# FRDM-Robot-Rev2_1.net
KiCad netlist of a schematic drawn in EAGLE
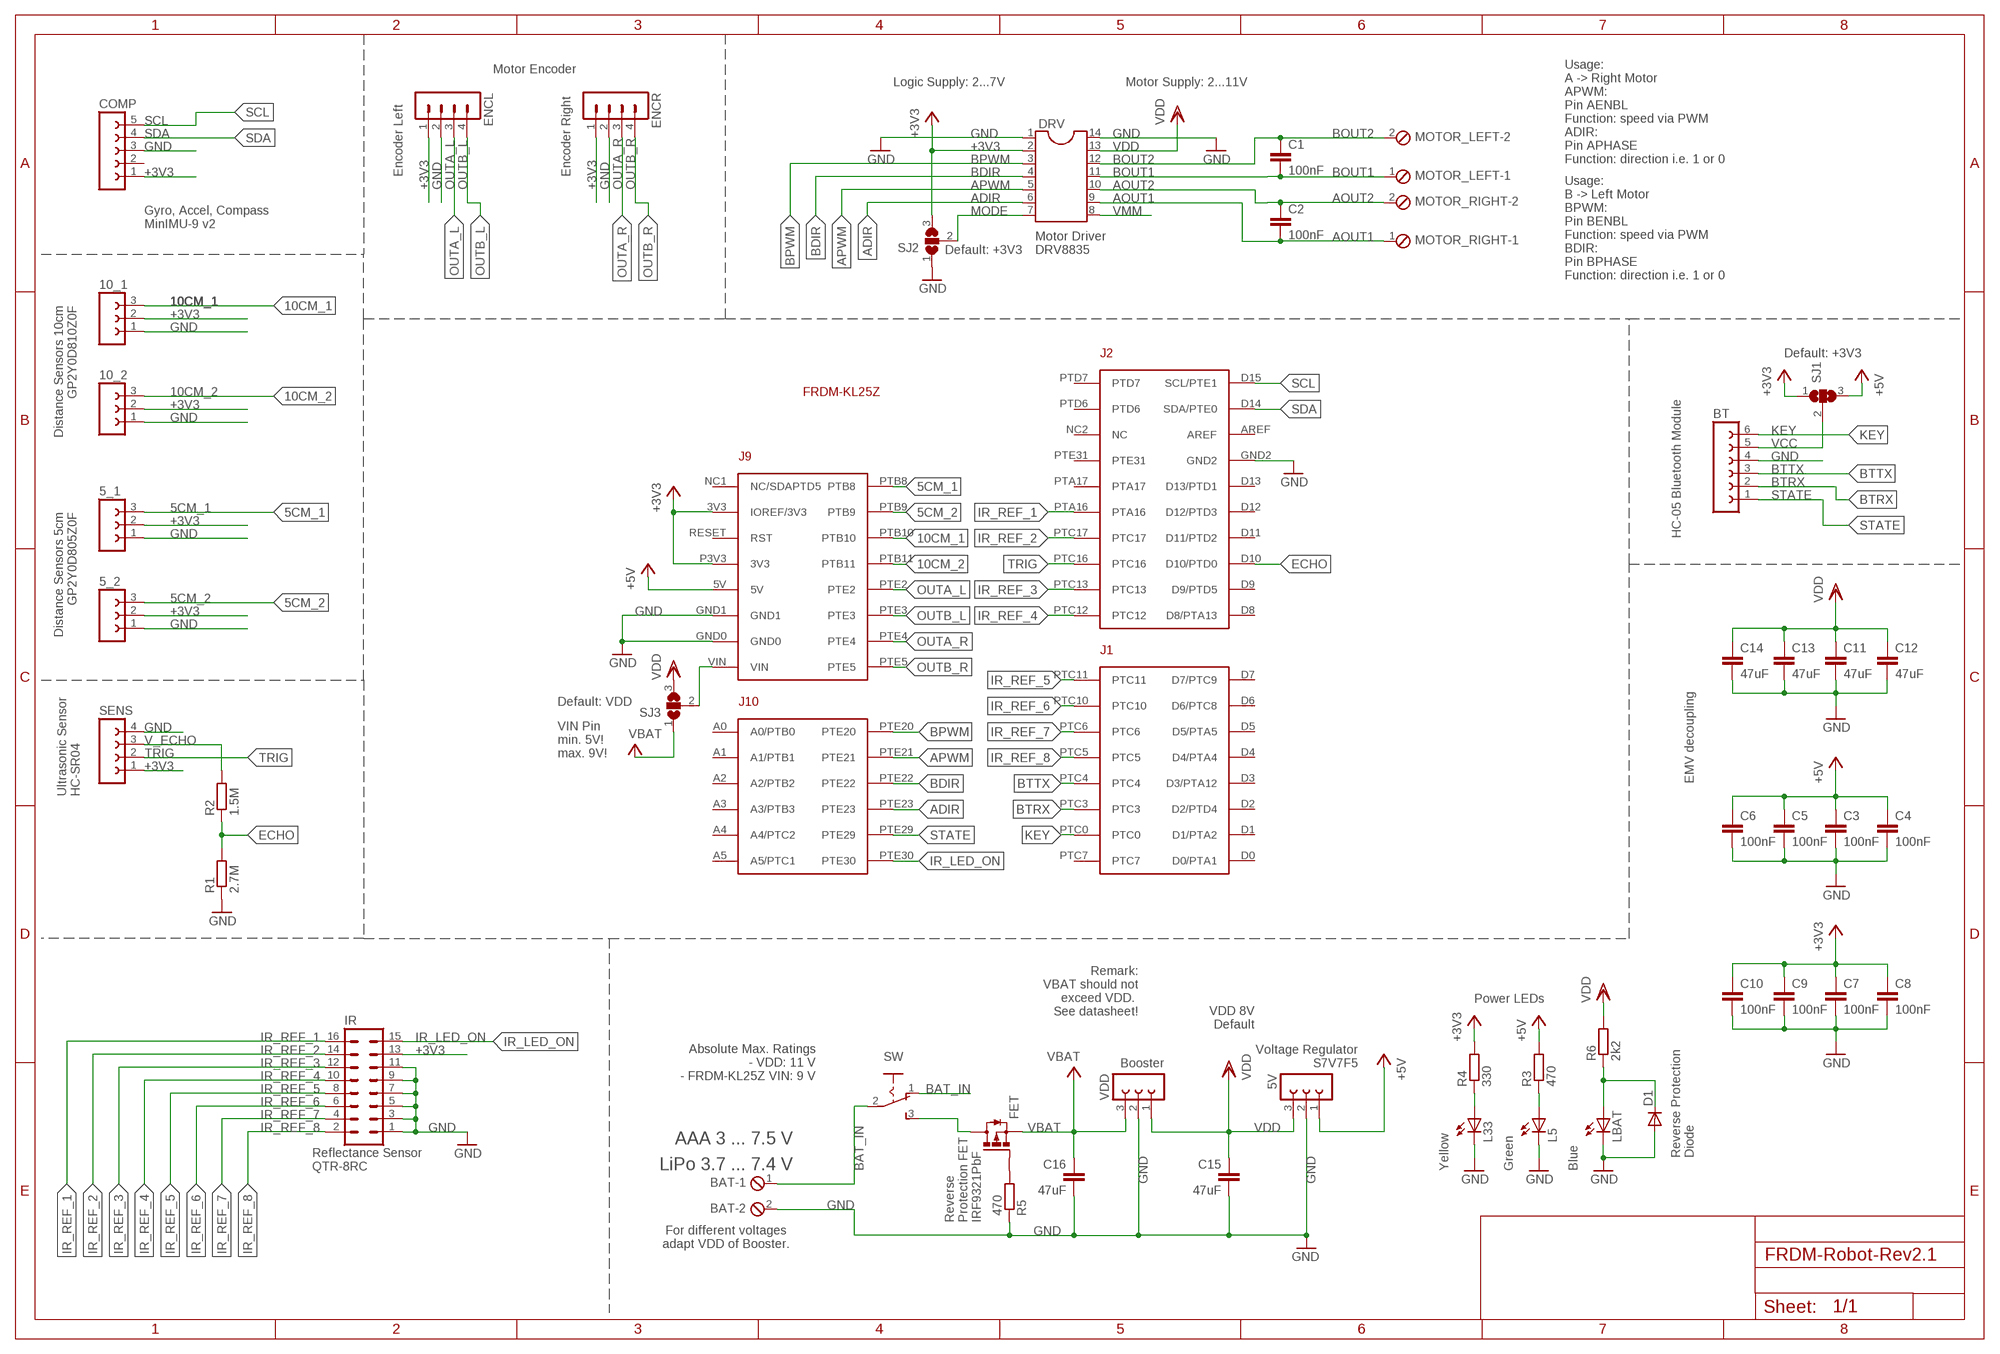
[diagram p0: schematic, sheet 1]

(export (version "E")
  (design (tool "Eeschema 10.0.6"))
  (components
    (comp (ref "5V")
      (value "FE03-1")
      (footprint "eagle-import:FE03-1")
      (libsource (lib "eagle-import") (part "FE03-1"))
    )
    (comp (ref "5_1")
      (value "FE03-1")
      (footprint "eagle-import:FE03-1")
      (libsource (lib "eagle-import") (part "FE03-1"))
    )
    (comp (ref "5_2")
      (value "FE03-1")
      (footprint "eagle-import:FE03-1")
      (libsource (lib "eagle-import") (part "FE03-1"))
    )
    (comp (ref "10_1")
      (value "FE03-1")
      (footprint "eagle-import:FE03-1")
      (libsource (lib "eagle-import") (part "FE03-1"))
    )
    (comp (ref "10_2")
      (value "FE03-1")
      (footprint "eagle-import:FE03-1")
      (libsource (lib "eagle-import") (part "FE03-1"))
    )
    (comp (ref "BAT")
      (value "MPT2")
      (footprint "eagle-import:2POL254")
      (libsource (lib "eagle-import") (part "MPT2"))
    )
    (comp (ref "BT")
      (value "FE06-1")
      (footprint "eagle-import:FE06")
      (libsource (lib "eagle-import") (part "FE06-1"))
    )
    (comp (ref "C1")
      (value "100nF")
      (footprint "eagle-import:C0805")
      (libsource (lib "eagle-import") (part "C-EUC0805"))
    )
    (comp (ref "C2")
      (value "100nF")
      (footprint "eagle-import:C0805")
      (libsource (lib "eagle-import") (part "C-EUC0805"))
    )
    (comp (ref "C3")
      (value "100nF")
      (footprint "eagle-import:C0805")
      (libsource (lib "eagle-import") (part "C-EUC0805"))
    )
    (comp (ref "C4")
      (value "100nF")
      (footprint "eagle-import:C0805")
      (libsource (lib "eagle-import") (part "C-EUC0805"))
    )
    (comp (ref "C5")
      (value "100nF")
      (footprint "eagle-import:C0805")
      (libsource (lib "eagle-import") (part "C-EUC0805"))
    )
    (comp (ref "C6")
      (value "100nF")
      (footprint "eagle-import:C0805")
      (libsource (lib "eagle-import") (part "C-EUC0805"))
    )
    (comp (ref "C7")
      (value "100nF")
      (footprint "eagle-import:C0805")
      (libsource (lib "eagle-import") (part "C-EUC0805"))
    )
    (comp (ref "C8")
      (value "100nF")
      (footprint "eagle-import:C0805")
      (libsource (lib "eagle-import") (part "C-EUC0805"))
    )
    (comp (ref "C9")
      (value "100nF")
      (footprint "eagle-import:C0805")
      (libsource (lib "eagle-import") (part "C-EUC0805"))
    )
    (comp (ref "C10")
      (value "100nF")
      (footprint "eagle-import:C0805")
      (libsource (lib "eagle-import") (part "C-EUC0805"))
    )
    (comp (ref "C11")
      (value "47uF")
      (footprint "eagle-import:C0805")
      (libsource (lib "eagle-import") (part "C-EUC0805"))
    )
    (comp (ref "C12")
      (value "47uF")
      (footprint "eagle-import:C0805")
      (libsource (lib "eagle-import") (part "C-EUC0805"))
    )
    (comp (ref "C13")
      (value "47uF")
      (footprint "eagle-import:C0805")
      (libsource (lib "eagle-import") (part "C-EUC0805"))
    )
    (comp (ref "C14")
      (value "47uF")
      (footprint "eagle-import:C0805")
      (libsource (lib "eagle-import") (part "C-EUC0805"))
    )
    (comp (ref "C15")
      (value "47uF")
      (footprint "eagle-import:C0805")
      (libsource (lib "eagle-import") (part "C-EUC0805"))
    )
    (comp (ref "C16")
      (value "47uF")
      (footprint "eagle-import:C0805")
      (libsource (lib "eagle-import") (part "C-EUC0805"))
    )
    (comp (ref "COMP")
      (value "FE05-1")
      (footprint "eagle-import:FE05-1")
      (libsource (lib "eagle-import") (part "FE05-1"))
    )
    (comp (ref "D1")
      (value "DIODE-SOD123")
      (footprint "eagle-import:SOD123")
      (libsource (lib "eagle-import") (part "DIODE-SOD123"))
    )
    (comp (ref "DRV")
      (value "DIL14")
      (footprint "eagle-import:DIL14")
      (libsource (lib "eagle-import") (part "DIL14"))
    )
    (comp (ref "ENCL")
      (value "MA04-1")
      (footprint "eagle-import:MA04-1")
      (libsource (lib "eagle-import") (part "MA04-1"))
    )
    (comp (ref "ENCR")
      (value "MA04-1")
      (footprint "eagle-import:MA04-1")
      (libsource (lib "eagle-import") (part "MA04-1"))
    )
    (comp (ref "FET")
      (value "P-MOSFET-SO8")
      (footprint "eagle-import:SO-08")
      (libsource (lib "eagle-import") (part "P-MOSFET-SO8"))
    )
    (comp (ref "FRDM1")
      (value "FRDM-KL25ZARDUINO")
      (footprint "eagle-import:FRDM-KL25Z")
      (libsource (lib "eagle-import") (part "FRDM-KL25ZARDUINO"))
    )
    (comp (ref "IR")
      (value "MA08-2")
      (footprint "eagle-import:MA08-2")
      (libsource (lib "eagle-import") (part "MA08-2"))
    )
    (comp (ref "L5")
      (value "LEDCHIP-LED0603")
      (footprint "eagle-import:CHIP-LED0603")
      (libsource (lib "eagle-import") (part "LEDCHIP-LED0603"))
    )
    (comp (ref "L33")
      (value "LEDCHIP-LED0603")
      (footprint "eagle-import:CHIP-LED0603")
      (libsource (lib "eagle-import") (part "LEDCHIP-LED0603"))
    )
    (comp (ref "LBAT")
      (value "LEDCHIP-LED0603")
      (footprint "eagle-import:CHIP-LED0603")
      (libsource (lib "eagle-import") (part "LEDCHIP-LED0603"))
    )
    (comp (ref "MOTOR_LEFT")
      (value "MPT2")
      (footprint "eagle-import:2POL254")
      (libsource (lib "eagle-import") (part "MPT2"))
    )
    (comp (ref "MOTOR_RIGHT")
      (value "MPT2")
      (footprint "eagle-import:2POL254")
      (libsource (lib "eagle-import") (part "MPT2"))
    )
    (comp (ref "R1")
      (value "2.7M")
      (footprint "eagle-import:M0805")
      (libsource (lib "eagle-import") (part "R-EU_M0805"))
    )
    (comp (ref "R2")
      (value "1.5M")
      (footprint "eagle-import:M0805")
      (libsource (lib "eagle-import") (part "R-EU_M0805"))
    )
    (comp (ref "R3")
      (value "470")
      (footprint "eagle-import:M0805")
      (libsource (lib "eagle-import") (part "R-EU_M0805"))
    )
    (comp (ref "R4")
      (value "330")
      (footprint "eagle-import:M0805")
      (libsource (lib "eagle-import") (part "R-EU_M0805"))
    )
    (comp (ref "R5")
      (value "470")
      (footprint "eagle-import:M0805")
      (libsource (lib "eagle-import") (part "R-EU_M0805"))
    )
    (comp (ref "R6")
      (value "2k2")
      (footprint "eagle-import:M0805")
      (libsource (lib "eagle-import") (part "R-EU_M0805"))
    )
    (comp (ref "SENS")
      (value "FE04-1")
      (footprint "eagle-import:FE04-1")
      (libsource (lib "eagle-import") (part "FE04-1"))
    )
    (comp (ref "SJ1")
      (value "SJ2W")
      (footprint "eagle-import:SJ_2")
      (libsource (lib "eagle-import") (part "SJ2W"))
    )
    (comp (ref "SJ2")
      (value "SJ2W")
      (footprint "eagle-import:SJ_2")
      (libsource (lib "eagle-import") (part "SJ2W"))
    )
    (comp (ref "SJ3")
      (value "SJ2W")
      (footprint "eagle-import:SJ_2")
      (libsource (lib "eagle-import") (part "SJ2W"))
    )
    (comp (ref "SW")
      (value "KNITTER-MFP106D")
      (footprint "eagle-import:KNITTER-MFP106D")
      (libsource (lib "eagle-import") (part "KNITTER-MFP106D"))
    )
    (comp (ref "VDD")
      (value "FE03-1")
      (footprint "eagle-import:FE03-1")
      (libsource (lib "eagle-import") (part "FE03-1"))
    )
  )
  (nets
    (net (code "1") (name "+3V3") (class "Default")
      (node (ref "10_1") (pin "2") (pinfunction "2_2") (pintype "passive"))
      (node (ref "10_2") (pin "2") (pinfunction "2_2") (pintype "passive"))
      (node (ref "5_1") (pin "2") (pinfunction "2_2") (pintype "passive"))
      (node (ref "5_2") (pin "2") (pinfunction "2_2") (pintype "passive"))
      (node (ref "C10") (pin "1") (pinfunction "1_1") (pintype "passive"))
      (node (ref "C7") (pin "1") (pinfunction "1_1") (pintype "passive"))
      (node (ref "C8") (pin "1") (pinfunction "1_1") (pintype "passive"))
      (node (ref "C9") (pin "1") (pinfunction "1_1") (pintype "passive"))
      (node (ref "COMP") (pin "1") (pinfunction "1_1") (pintype "passive"))
      (node (ref "DRV") (pin "2") (pinfunction "2_2") (pintype "passive"))
      (node (ref "ENCL") (pin "1") (pinfunction "1_1") (pintype "passive"))
      (node (ref "ENCR") (pin "1") (pinfunction "1_1") (pintype "passive"))
      (node (ref "FRDM1") (pin "3V3") (pinfunction "IOREF/3V3_3V3") (pintype "bidirectional"))
      (node (ref "FRDM1") (pin "P3V3") (pinfunction "3V3_P3V3") (pintype "bidirectional"))
      (node (ref "IR") (pin "13") (pinfunction "13_13") (pintype "passive"))
      (node (ref "R4") (pin "2") (pinfunction "2_2") (pintype "passive"))
      (node (ref "SENS") (pin "1") (pinfunction "1_1") (pintype "passive"))
      (node (ref "SJ1") (pin "1") (pinfunction "1_1") (pintype "passive"))
      (node (ref "SJ2") (pin "3") (pinfunction "3_3") (pintype "passive"))
    )
    (net (code "2") (name "+5V") (class "Default")
      (node (ref "5V") (pin "1") (pinfunction "1_1") (pintype "passive"))
      (node (ref "C3") (pin "1") (pinfunction "1_1") (pintype "passive"))
      (node (ref "C4") (pin "1") (pinfunction "1_1") (pintype "passive"))
      (node (ref "C5") (pin "1") (pinfunction "1_1") (pintype "passive"))
      (node (ref "C6") (pin "1") (pinfunction "1_1") (pintype "passive"))
      (node (ref "FRDM1") (pin "5V") (pinfunction "5V_5V") (pintype "bidirectional"))
      (node (ref "R3") (pin "2") (pinfunction "2_2") (pintype "passive"))
      (node (ref "SJ1") (pin "3") (pinfunction "3_3") (pintype "passive"))
    )
    (net (code "3") (name "/AOUT1") (class "Default")
      (node (ref "C2") (pin "2") (pinfunction "2_2") (pintype "passive"))
      (node (ref "DRV") (pin "9") (pinfunction "9_9") (pintype "passive"))
      (node (ref "MOTOR_RIGHT") (pin "1") (pinfunction "1_1") (pintype "passive"))
    )
    (net (code "4") (name "/AOUT2") (class "Default")
      (node (ref "C2") (pin "1") (pinfunction "1_1") (pintype "passive"))
      (node (ref "DRV") (pin "10") (pinfunction "10_10") (pintype "passive"))
      (node (ref "MOTOR_RIGHT") (pin "2") (pinfunction "1_2") (pintype "passive"))
    )
    (net (code "5") (name "/BAT_IN") (class "Default")
      (node (ref "BAT") (pin "1") (pinfunction "1_1") (pintype "passive"))
      (node (ref "SW") (pin "1") (pinfunction "O_1") (pintype "passive"))
      (node (ref "SW") (pin "2") (pinfunction "P_2") (pintype "passive"))
    )
    (net (code "6") (name "/BOUT1") (class "Default")
      (node (ref "C1") (pin "2") (pinfunction "2_2") (pintype "passive"))
      (node (ref "DRV") (pin "11") (pinfunction "11_11") (pintype "passive"))
      (node (ref "MOTOR_LEFT") (pin "1") (pinfunction "1_1") (pintype "passive"))
    )
    (net (code "7") (name "/BOUT2") (class "Default")
      (node (ref "C1") (pin "1") (pinfunction "1_1") (pintype "passive"))
      (node (ref "DRV") (pin "12") (pinfunction "12_12") (pintype "passive"))
      (node (ref "MOTOR_LEFT") (pin "2") (pinfunction "1_2") (pintype "passive"))
    )
    (net (code "8") (name "/MODE") (class "Default")
      (node (ref "DRV") (pin "7") (pinfunction "7_7") (pintype "passive"))
      (node (ref "SJ2") (pin "2") (pinfunction "2_2") (pintype "passive"))
    )
    (net (code "9") (name "/VCC") (class "Default")
      (node (ref "BT") (pin "5") (pinfunction "5_5") (pintype "passive"))
      (node (ref "SJ1") (pin "2") (pinfunction "2_2") (pintype "passive"))
    )
    (net (code "10") (name "/VMM") (class "Default")
      (node (ref "DRV") (pin "8") (pinfunction "8_8") (pintype "passive"))
    )
    (net (code "11") (name "/V_ECHO") (class "Default")
      (node (ref "R2") (pin "2") (pinfunction "2_2") (pintype "passive"))
      (node (ref "SENS") (pin "3") (pinfunction "3_3") (pintype "passive"))
    )
    (net (code "12") (name "5CM_1") (class "Default")
      (node (ref "5_1") (pin "3") (pinfunction "3_3") (pintype "passive"))
      (node (ref "FRDM1") (pin "PTB8") (pinfunction "PTB8_PTB8") (pintype "bidirectional"))
    )
    (net (code "13") (name "5CM_2") (class "Default")
      (node (ref "5_2") (pin "3") (pinfunction "3_3") (pintype "passive"))
      (node (ref "FRDM1") (pin "PTB9") (pinfunction "PTB9_PTB9") (pintype "bidirectional"))
    )
    (net (code "14") (name "10CM_1") (class "Default")
      (node (ref "10_1") (pin "3") (pinfunction "3_3") (pintype "passive"))
      (node (ref "FRDM1") (pin "PTB10") (pinfunction "PTB10_PTB10") (pintype "bidirectional"))
    )
    (net (code "15") (name "10CM_2") (class "Default")
      (node (ref "10_2") (pin "3") (pinfunction "3_3") (pintype "passive"))
      (node (ref "FRDM1") (pin "PTB11") (pinfunction "PTB11_PTB11") (pintype "bidirectional"))
    )
    (net (code "16") (name "ADIR") (class "Default")
      (node (ref "DRV") (pin "6") (pinfunction "6_6") (pintype "passive"))
      (node (ref "FRDM1") (pin "PTE23") (pinfunction "PTE23_PTE23") (pintype "bidirectional"))
    )
    (net (code "17") (name "APWM") (class "Default")
      (node (ref "DRV") (pin "5") (pinfunction "5_5") (pintype "passive"))
      (node (ref "FRDM1") (pin "PTE21") (pinfunction "PTE21_PTE21") (pintype "bidirectional"))
    )
    (net (code "18") (name "BDIR") (class "Default")
      (node (ref "DRV") (pin "4") (pinfunction "4_4") (pintype "passive"))
      (node (ref "FRDM1") (pin "PTE22") (pinfunction "PTE22_PTE22") (pintype "bidirectional"))
    )
    (net (code "19") (name "BPWM") (class "Default")
      (node (ref "DRV") (pin "3") (pinfunction "3_3") (pintype "passive"))
      (node (ref "FRDM1") (pin "PTE20") (pinfunction "PTE20_PTE20") (pintype "bidirectional"))
    )
    (net (code "20") (name "BTRX") (class "Default")
      (node (ref "BT") (pin "2") (pinfunction "2_2") (pintype "passive"))
      (node (ref "FRDM1") (pin "PTC3") (pinfunction "PTC3_PTC3") (pintype "bidirectional"))
    )
    (net (code "21") (name "BTTX") (class "Default")
      (node (ref "BT") (pin "3") (pinfunction "3_3") (pintype "passive"))
      (node (ref "FRDM1") (pin "PTC4") (pinfunction "PTC4_PTC4") (pintype "bidirectional"))
    )
    (net (code "22") (name "ECHO") (class "Default")
      (node (ref "FRDM1") (pin "D10") (pinfunction "D10/PTD0_D10") (pintype "bidirectional"))
      (node (ref "R1") (pin "2") (pinfunction "2_2") (pintype "passive"))
      (node (ref "R2") (pin "1") (pinfunction "1_1") (pintype "passive"))
    )
    (net (code "23") (name "GND") (class "Default")
      (node (ref "10_1") (pin "1") (pinfunction "1_1") (pintype "passive"))
      (node (ref "10_2") (pin "1") (pinfunction "1_1") (pintype "passive"))
      (node (ref "5V") (pin "2") (pinfunction "2_2") (pintype "passive"))
      (node (ref "5_1") (pin "1") (pinfunction "1_1") (pintype "passive"))
      (node (ref "5_2") (pin "1") (pinfunction "1_1") (pintype "passive"))
      (node (ref "BAT") (pin "2") (pinfunction "1_2") (pintype "passive"))
      (node (ref "BT") (pin "4") (pinfunction "4_4") (pintype "passive"))
      (node (ref "C10") (pin "2") (pinfunction "2_2") (pintype "passive"))
      (node (ref "C11") (pin "2") (pinfunction "2_2") (pintype "passive"))
      (node (ref "C12") (pin "2") (pinfunction "2_2") (pintype "passive"))
      (node (ref "C13") (pin "2") (pinfunction "2_2") (pintype "passive"))
      (node (ref "C14") (pin "2") (pinfunction "2_2") (pintype "passive"))
      (node (ref "C15") (pin "2") (pinfunction "2_2") (pintype "passive"))
      (node (ref "C16") (pin "2") (pinfunction "2_2") (pintype "passive"))
      (node (ref "C3") (pin "2") (pinfunction "2_2") (pintype "passive"))
      (node (ref "C4") (pin "2") (pinfunction "2_2") (pintype "passive"))
      (node (ref "C5") (pin "2") (pinfunction "2_2") (pintype "passive"))
      (node (ref "C6") (pin "2") (pinfunction "2_2") (pintype "passive"))
      (node (ref "C7") (pin "2") (pinfunction "2_2") (pintype "passive"))
      (node (ref "C8") (pin "2") (pinfunction "2_2") (pintype "passive"))
      (node (ref "C9") (pin "2") (pinfunction "2_2") (pintype "passive"))
      (node (ref "COMP") (pin "3") (pinfunction "3_3") (pintype "passive"))
      (node (ref "D1") (pin "A") (pinfunction "A_A") (pintype "passive"))
      (node (ref "DRV") (pin "1") (pinfunction "1_1") (pintype "passive"))
      (node (ref "DRV") (pin "14") (pinfunction "14_14") (pintype "passive"))
      (node (ref "ENCL") (pin "2") (pinfunction "2_2") (pintype "passive"))
      (node (ref "ENCR") (pin "2") (pinfunction "2_2") (pintype "passive"))
      (node (ref "FRDM1") (pin "GND0") (pinfunction "GND0_GND0") (pintype "bidirectional"))
      (node (ref "FRDM1") (pin "GND1") (pinfunction "GND1_GND1") (pintype "bidirectional"))
      (node (ref "FRDM1") (pin "GND2") (pinfunction "GND2_GND2") (pintype "bidirectional"))
      (node (ref "IR") (pin "1") (pinfunction "1_1") (pintype "passive"))
      (node (ref "IR") (pin "11") (pinfunction "11_11") (pintype "passive"))
      (node (ref "IR") (pin "3") (pinfunction "3_3") (pintype "passive"))
      (node (ref "IR") (pin "5") (pinfunction "5_5") (pintype "passive"))
      (node (ref "IR") (pin "7") (pinfunction "7_7") (pintype "passive"))
      (node (ref "IR") (pin "9") (pinfunction "9_9") (pintype "passive"))
      (node (ref "L33") (pin "C") (pinfunction "C_C") (pintype "passive"))
      (node (ref "L5") (pin "C") (pinfunction "C_C") (pintype "passive"))
      (node (ref "LBAT") (pin "C") (pinfunction "C_C") (pintype "passive"))
      (node (ref "R1") (pin "1") (pinfunction "1_1") (pintype "passive"))
      (node (ref "R5") (pin "1") (pinfunction "1_1") (pintype "passive"))
      (node (ref "SENS") (pin "4") (pinfunction "4_4") (pintype "passive"))
      (node (ref "SJ2") (pin "1") (pinfunction "1_1") (pintype "passive"))
      (node (ref "VDD") (pin "2") (pinfunction "2_2") (pintype "passive"))
    )
    (net (code "24") (name "IR_LED_ON") (class "Default")
      (node (ref "FRDM1") (pin "PTE30") (pinfunction "PTE30_PTE30") (pintype "bidirectional"))
      (node (ref "IR") (pin "15") (pinfunction "15_15") (pintype "passive"))
    )
    (net (code "25") (name "IR_REF_1") (class "Default")
      (node (ref "FRDM1") (pin "PTA16") (pinfunction "PTA16_PTA16") (pintype "bidirectional"))
      (node (ref "IR") (pin "16") (pinfunction "16_16") (pintype "passive"))
    )
    (net (code "26") (name "IR_REF_2") (class "Default")
      (node (ref "FRDM1") (pin "PTC17") (pinfunction "PTC17_PTC17") (pintype "bidirectional"))
      (node (ref "IR") (pin "14") (pinfunction "14_14") (pintype "passive"))
    )
    (net (code "27") (name "IR_REF_3") (class "Default")
      (node (ref "FRDM1") (pin "PTC13") (pinfunction "PTC13_PTC13") (pintype "bidirectional"))
      (node (ref "IR") (pin "12") (pinfunction "12_12") (pintype "passive"))
    )
    (net (code "28") (name "IR_REF_4") (class "Default")
      (node (ref "FRDM1") (pin "PTC12") (pinfunction "PTC12_PTC12") (pintype "bidirectional"))
      (node (ref "IR") (pin "10") (pinfunction "10_10") (pintype "passive"))
    )
    (net (code "29") (name "IR_REF_5") (class "Default")
      (node (ref "FRDM1") (pin "PTC11") (pinfunction "PTC11_PTC11") (pintype "bidirectional"))
      (node (ref "IR") (pin "8") (pinfunction "8_8") (pintype "passive"))
    )
    (net (code "30") (name "IR_REF_6") (class "Default")
      (node (ref "FRDM1") (pin "PTC10") (pinfunction "PTC10_PTC10") (pintype "bidirectional"))
      (node (ref "IR") (pin "6") (pinfunction "6_6") (pintype "passive"))
    )
    (net (code "31") (name "IR_REF_7") (class "Default")
      (node (ref "FRDM1") (pin "PTC6") (pinfunction "PTC6_PTC6") (pintype "bidirectional"))
      (node (ref "IR") (pin "4") (pinfunction "4_4") (pintype "passive"))
    )
    (net (code "32") (name "IR_REF_8") (class "Default")
      (node (ref "FRDM1") (pin "PTC5") (pinfunction "PTC5_PTC5") (pintype "bidirectional"))
      (node (ref "IR") (pin "2") (pinfunction "2_2") (pintype "passive"))
    )
    (net (code "33") (name "KEY") (class "Default")
      (node (ref "BT") (pin "6") (pinfunction "6_6") (pintype "passive"))
      (node (ref "FRDM1") (pin "PTC0") (pinfunction "PTC0_PTC0") (pintype "bidirectional"))
    )
    (net (code "34") (name "Net-(D1-PadC)") (class "Default")
      (node (ref "D1") (pin "C") (pinfunction "C_C") (pintype "passive"))
      (node (ref "LBAT") (pin "A") (pinfunction "A_A") (pintype "passive"))
      (node (ref "R6") (pin "1") (pinfunction "1_1") (pintype "passive"))
    )
    (net (code "35") (name "Net-(FET-G)") (class "Default")
      (node (ref "FET") (pin "4") (pinfunction "G_4") (pintype "passive"))
      (node (ref "R5") (pin "2") (pinfunction "2_2") (pintype "passive"))
    )
    (net (code "36") (name "Net-(FRDM1-PadVIN)") (class "Default")
      (node (ref "FRDM1") (pin "VIN") (pinfunction "VIN_VIN") (pintype "bidirectional"))
      (node (ref "SJ3") (pin "2") (pinfunction "2_2") (pintype "passive"))
    )
    (net (code "37") (name "Net-(L5-PadA)") (class "Default")
      (node (ref "L5") (pin "A") (pinfunction "A_A") (pintype "passive"))
      (node (ref "R3") (pin "1") (pinfunction "1_1") (pintype "passive"))
    )
    (net (code "38") (name "Net-(L33-PadA)") (class "Default")
      (node (ref "L33") (pin "A") (pinfunction "A_A") (pintype "passive"))
      (node (ref "R4") (pin "1") (pinfunction "1_1") (pintype "passive"))
    )
    (net (code "39") (name "Net-(SW-S)") (class "Default")
      (node (ref "FET") (pin "5") (pinfunction "D_5") (pintype "passive"))
      (node (ref "FET") (pin "6") (pinfunction "D_6") (pintype "passive"))
      (node (ref "FET") (pin "7") (pinfunction "D_7") (pintype "passive"))
      (node (ref "FET") (pin "8") (pinfunction "D_8") (pintype "passive"))
      (node (ref "SW") (pin "3") (pinfunction "S_3") (pintype "passive"))
    )
    (net (code "40") (name "OUTA_L") (class "Default")
      (node (ref "ENCL") (pin "3") (pinfunction "3_3") (pintype "passive"))
      (node (ref "FRDM1") (pin "PTE2") (pinfunction "PTE2_PTE2") (pintype "bidirectional"))
    )
    (net (code "41") (name "OUTA_R") (class "Default")
      (node (ref "ENCR") (pin "3") (pinfunction "3_3") (pintype "passive"))
      (node (ref "FRDM1") (pin "PTE4") (pinfunction "PTE4_PTE4") (pintype "bidirectional"))
    )
    (net (code "42") (name "OUTB_L") (class "Default")
      (node (ref "ENCL") (pin "4") (pinfunction "4_4") (pintype "passive"))
      (node (ref "FRDM1") (pin "PTE3") (pinfunction "PTE3_PTE3") (pintype "bidirectional"))
    )
    (net (code "43") (name "OUTB_R") (class "Default")
      (node (ref "ENCR") (pin "4") (pinfunction "4_4") (pintype "passive"))
      (node (ref "FRDM1") (pin "PTE5") (pinfunction "PTE5_PTE5") (pintype "bidirectional"))
    )
    (net (code "44") (name "SCL") (class "Default")
      (node (ref "COMP") (pin "5") (pinfunction "5_5") (pintype "passive"))
      (node (ref "FRDM1") (pin "D15") (pinfunction "SCL/PTE1_D15") (pintype "bidirectional"))
    )
    (net (code "45") (name "SDA") (class "Default")
      (node (ref "COMP") (pin "4") (pinfunction "4_4") (pintype "passive"))
      (node (ref "FRDM1") (pin "D14") (pinfunction "SDA/PTE0_D14") (pintype "bidirectional"))
    )
    (net (code "46") (name "STATE") (class "Default")
      (node (ref "BT") (pin "1") (pinfunction "1_1") (pintype "passive"))
      (node (ref "FRDM1") (pin "PTE29") (pinfunction "PTE29_PTE29") (pintype "bidirectional"))
    )
    (net (code "47") (name "TRIG") (class "Default")
      (node (ref "FRDM1") (pin "PTC16") (pinfunction "PTC16_PTC16") (pintype "bidirectional"))
      (node (ref "SENS") (pin "2") (pinfunction "2_2") (pintype "passive"))
    )
    (net (code "48") (name "VBAT") (class "Default")
      (node (ref "C16") (pin "1") (pinfunction "1_1") (pintype "passive"))
      (node (ref "FET") (pin "1") (pinfunction "S_1") (pintype "passive"))
      (node (ref "FET") (pin "2") (pinfunction "S_2") (pintype "passive"))
      (node (ref "FET") (pin "3") (pinfunction "S_3") (pintype "passive"))
      (node (ref "SJ3") (pin "1") (pinfunction "1_1") (pintype "passive"))
      (node (ref "VDD") (pin "3") (pinfunction "3_3") (pintype "passive"))
    )
    (net (code "49") (name "VDD") (class "Default")
      (node (ref "5V") (pin "3") (pinfunction "3_3") (pintype "passive"))
      (node (ref "C11") (pin "1") (pinfunction "1_1") (pintype "passive"))
      (node (ref "C12") (pin "1") (pinfunction "1_1") (pintype "passive"))
      (node (ref "C13") (pin "1") (pinfunction "1_1") (pintype "passive"))
      (node (ref "C14") (pin "1") (pinfunction "1_1") (pintype "passive"))
      (node (ref "C15") (pin "1") (pinfunction "1_1") (pintype "passive"))
      (node (ref "DRV") (pin "13") (pinfunction "13_13") (pintype "passive"))
      (node (ref "R6") (pin "2") (pinfunction "2_2") (pintype "passive"))
      (node (ref "SJ3") (pin "3") (pinfunction "3_3") (pintype "passive"))
      (node (ref "VDD") (pin "1") (pinfunction "1_1") (pintype "passive"))
    )
    (net (code "50") (name "unconnected-(COMP-Pad2)") (class "Default")
      (node (ref "COMP") (pin "2") (pinfunction "2_2") (pintype "passive"))
    )
    (net (code "51") (name "unconnected-(FRDM1-A0{slash}PTB0-PadA0)") (class "Default")
      (node (ref "FRDM1") (pin "A0") (pinfunction "A0/PTB0_A0") (pintype "bidirectional"))
    )
    (net (code "52") (name "unconnected-(FRDM1-A1{slash}PTB1-PadA1)") (class "Default")
      (node (ref "FRDM1") (pin "A1") (pinfunction "A1/PTB1_A1") (pintype "bidirectional"))
    )
    (net (code "53") (name "unconnected-(FRDM1-A2{slash}PTB2-PadA2)") (class "Default")
      (node (ref "FRDM1") (pin "A2") (pinfunction "A2/PTB2_A2") (pintype "bidirectional"))
    )
    (net (code "54") (name "unconnected-(FRDM1-A3{slash}PTB3-PadA3)") (class "Default")
      (node (ref "FRDM1") (pin "A3") (pinfunction "A3/PTB3_A3") (pintype "bidirectional"))
    )
    (net (code "55") (name "unconnected-(FRDM1-A4{slash}PTC2-PadA4)") (class "Default")
      (node (ref "FRDM1") (pin "A4") (pinfunction "A4/PTC2_A4") (pintype "bidirectional"))
    )
    (net (code "56") (name "unconnected-(FRDM1-A5{slash}PTC1-PadA5)") (class "Default")
      (node (ref "FRDM1") (pin "A5") (pinfunction "A5/PTC1_A5") (pintype "bidirectional"))
    )
    (net (code "57") (name "unconnected-(FRDM1-D0{slash}PTA1-PadD0)") (class "Default")
      (node (ref "FRDM1") (pin "D0") (pinfunction "D0/PTA1_D0") (pintype "bidirectional"))
    )
    (net (code "58") (name "unconnected-(FRDM1-D1{slash}PTA2-PadD1)") (class "Default")
      (node (ref "FRDM1") (pin "D1") (pinfunction "D1/PTA2_D1") (pintype "bidirectional"))
    )
    (net (code "59") (name "unconnected-(FRDM1-D2{slash}PTD4-PadD2)") (class "Default")
      (node (ref "FRDM1") (pin "D2") (pinfunction "D2/PTD4_D2") (pintype "bidirectional"))
    )
    (net (code "60") (name "unconnected-(FRDM1-D3{slash}PTA12-PadD3)") (class "Default")
      (node (ref "FRDM1") (pin "D3") (pinfunction "D3/PTA12_D3") (pintype "bidirectional"))
    )
    (net (code "61") (name "unconnected-(FRDM1-D4{slash}PTA4-PadD4)") (class "Default")
      (node (ref "FRDM1") (pin "D4") (pinfunction "D4/PTA4_D4") (pintype "bidirectional"))
    )
    (net (code "62") (name "unconnected-(FRDM1-D5{slash}PTA5-PadD5)") (class "Default")
      (node (ref "FRDM1") (pin "D5") (pinfunction "D5/PTA5_D5") (pintype "bidirectional"))
    )
    (net (code "63") (name "unconnected-(FRDM1-D6{slash}PTC8-PadD6)") (class "Default")
      (node (ref "FRDM1") (pin "D6") (pinfunction "D6/PTC8_D6") (pintype "bidirectional"))
    )
    (net (code "64") (name "unconnected-(FRDM1-D7{slash}PTC9-PadD7)") (class "Default")
      (node (ref "FRDM1") (pin "D7") (pinfunction "D7/PTC9_D7") (pintype "bidirectional"))
    )
    (net (code "65") (name "unconnected-(FRDM1-D8{slash}PTA13-PadD8)") (class "Default")
      (node (ref "FRDM1") (pin "D8") (pinfunction "D8/PTA13_D8") (pintype "bidirectional"))
    )
    (net (code "66") (name "unconnected-(FRDM1-D9{slash}PTD5-PadD9)") (class "Default")
      (node (ref "FRDM1") (pin "D9") (pinfunction "D9/PTD5_D9") (pintype "bidirectional"))
    )
    (net (code "67") (name "unconnected-(FRDM1-D11{slash}PTD2-PadD11)") (class "Default")
      (node (ref "FRDM1") (pin "D11") (pinfunction "D11/PTD2_D11") (pintype "bidirectional"))
    )
    (net (code "68") (name "unconnected-(FRDM1-D12{slash}PTD3-PadD12)") (class "Default")
      (node (ref "FRDM1") (pin "D12") (pinfunction "D12/PTD3_D12") (pintype "bidirectional"))
    )
    (net (code "69") (name "unconnected-(FRDM1-D13{slash}PTD1-PadD13)") (class "Default")
      (node (ref "FRDM1") (pin "D13") (pinfunction "D13/PTD1_D13") (pintype "bidirectional"))
    )
    (net (code "70") (name "unconnected-(FRDM1-NC-PadNC2)") (class "Default")
      (node (ref "FRDM1") (pin "NC2") (pinfunction "NC_NC2") (pintype "bidirectional"))
    )
    (net (code "71") (name "unconnected-(FRDM1-NC{slash}SDAPTD5-PadNC1)") (class "Default")
      (node (ref "FRDM1") (pin "NC1") (pinfunction "NC/SDAPTD5_NC1") (pintype "bidirectional"))
    )
    (net (code "72") (name "unconnected-(FRDM1-PadAREF)") (class "Default")
      (node (ref "FRDM1") (pin "AREF") (pinfunction "AREF_AREF") (pintype "bidirectional"))
    )
    (net (code "73") (name "unconnected-(FRDM1-PadPTA17)") (class "Default")
      (node (ref "FRDM1") (pin "PTA17") (pinfunction "PTA17_PTA17") (pintype "bidirectional"))
    )
    (net (code "74") (name "unconnected-(FRDM1-PadPTC7)") (class "Default")
      (node (ref "FRDM1") (pin "PTC7") (pinfunction "PTC7_PTC7") (pintype "bidirectional"))
    )
    (net (code "75") (name "unconnected-(FRDM1-PadPTD6)") (class "Default")
      (node (ref "FRDM1") (pin "PTD6") (pinfunction "PTD6_PTD6") (pintype "bidirectional"))
    )
    (net (code "76") (name "unconnected-(FRDM1-PadPTD7)") (class "Default")
      (node (ref "FRDM1") (pin "PTD7") (pinfunction "PTD7_PTD7") (pintype "bidirectional"))
    )
    (net (code "77") (name "unconnected-(FRDM1-PadPTE31)") (class "Default")
      (node (ref "FRDM1") (pin "PTE31") (pinfunction "PTE31_PTE31") (pintype "bidirectional"))
    )
    (net (code "78") (name "unconnected-(FRDM1-RST-PadRESET)") (class "Default")
      (node (ref "FRDM1") (pin "RESET") (pinfunction "RST_RESET") (pintype "bidirectional"))
    )
  )
)
